# Wacky_Racer_Schematic.net
KiCad netlist of a schematic drawn in Altium Designer
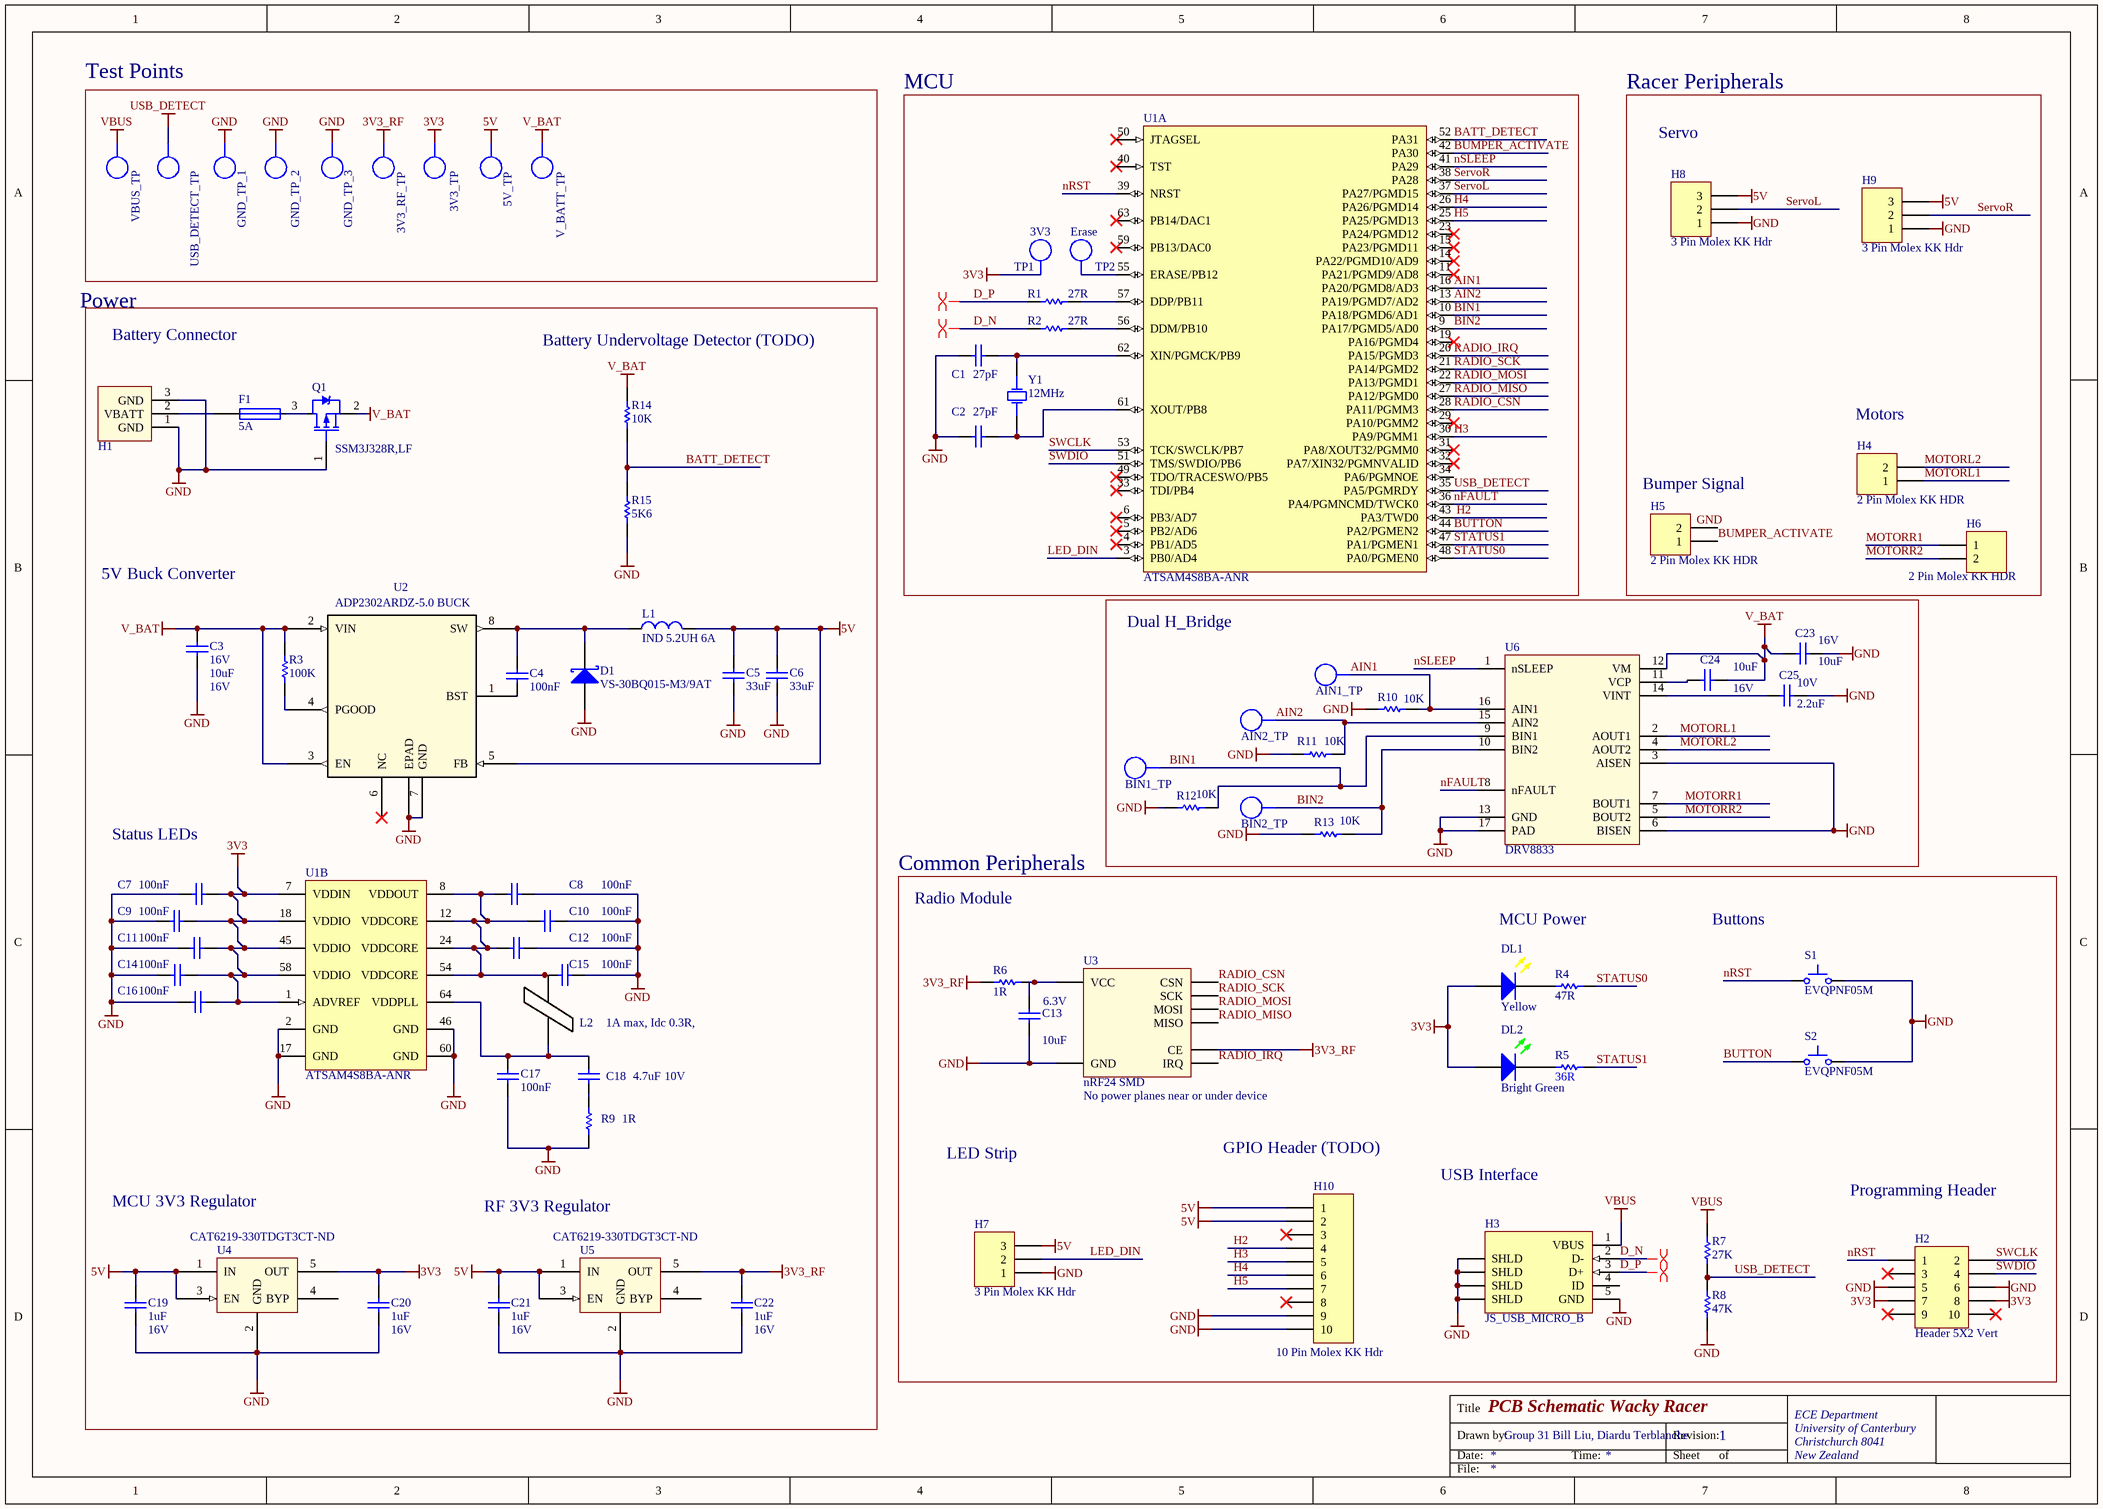
[diagram p0: Wacky Racer Schematic.schdoc]

(export (version "E")
  (design (tool "Eeschema 10.0.6"))
  (components
    (comp (ref "3V3_RF_TP")
      (value "TP")
      (footprint "TP_1206")
      (description "Test-Point 3.3x1.6x2.1mm SMD")
      (fields
        (field (name "MANUFACTURER") "Harwin Inc")
        (field (name "MANUFACTURER PART NUMBER") "S1751-46R")
      )
      (libsource (lib "ECE AD19Components_19V1") (part "TP_1206"))
    )
    (comp (ref "3V3_TP")
      (value "TP")
      (footprint "TP_1206")
      (description "Test-Point 3.3x1.6x2.1mm SMD")
      (fields
        (field (name "MANUFACTURER") "Harwin Inc")
        (field (name "MANUFACTURER PART NUMBER") "S1751-46R")
      )
      (libsource (lib "ECE AD19Components_19V1") (part "TP_1206"))
    )
    (comp (ref "5V_TP")
      (value "TP")
      (footprint "TP_1206")
      (description "Test-Point 3.3x1.6x2.1mm SMD")
      (fields
        (field (name "MANUFACTURER") "Harwin Inc")
        (field (name "MANUFACTURER PART NUMBER") "S1751-46R")
      )
      (libsource (lib "ECE AD19Components_19V1") (part "TP_1206"))
    )
    (comp (ref "AIN1_TP")
      (value "TP")
      (footprint "TP_1206")
      (description "Test-Point 3.3x1.6x2.1mm SMD")
      (fields
        (field (name "MANUFACTURER") "Harwin Inc")
        (field (name "MANUFACTURER PART NUMBER") "S1751-46R")
      )
      (libsource (lib "ECE AD19Components_19V1") (part "TP_1206"))
    )
    (comp (ref "AIN2_TP")
      (value "TP")
      (footprint "TP_1206")
      (description "Test-Point 3.3x1.6x2.1mm SMD")
      (fields
        (field (name "MANUFACTURER") "Harwin Inc")
        (field (name "MANUFACTURER PART NUMBER") "S1751-46R")
      )
      (libsource (lib "ECE AD19Components_19V1") (part "TP_1206"))
    )
    (comp (ref "BIN1_TP")
      (value "TP")
      (footprint "TP_1206")
      (description "Test-Point 3.3x1.6x2.1mm SMD")
      (fields
        (field (name "MANUFACTURER") "Harwin Inc")
        (field (name "MANUFACTURER PART NUMBER") "S1751-46R")
      )
      (libsource (lib "ECE AD19Components_19V1") (part "TP_1206"))
    )
    (comp (ref "BIN2_TP")
      (value "TP")
      (footprint "TP_1206")
      (description "Test-Point 3.3x1.6x2.1mm SMD")
      (fields
        (field (name "MANUFACTURER") "Harwin Inc")
        (field (name "MANUFACTURER PART NUMBER") "S1751-46R")
      )
      (libsource (lib "ECE AD19Components_19V1") (part "TP_1206"))
    )
    (comp (ref "C1")
      (value "27pF")
      (footprint "CAPC1608L")
      (description "CAP CER 27pF NPO/COG +-5% 50V 0603")
      (libsource (lib "ECE AD19Components_19V1") (part "CC_27pF_0603"))
    )
    (comp (ref "C2")
      (value "27pF")
      (footprint "CAPC1608L")
      (description "CAP CER 27pF NPO/COG +-5% 50V 0603")
      (libsource (lib "ECE AD19Components_19V1") (part "CC_27pF_0603"))
    )
    (comp (ref "C3")
      (value "10uF")
      (footprint "CAPC2012L")
      (description "CAP CER 10uF X5R 16V 0805")
      (fields
        (field (name "MANUFACTURER") "Samsung Electro-Mechanics")
        (field (name "MANUFACTURER PART NUMBER") "CL21A106KOQNNWE")
        (field (name "VOLTAGE - RATED") "16V")
        (field (name "MAX VOLTAGE") "16V")
      )
      (libsource (lib "ENCE461AD19_19V2") (part "CC_10uF_16V_0805"))
    )
    (comp (ref "C4")
      (value "100nF")
      (footprint "CAPC1608L")
      (description "CAP CER 100nF X7R +-10% 50V 0603")
      (libsource (lib "ECE AD19Components_19V1") (part "CC_100nF_0603"))
    )
    (comp (ref "C5")
      (value "33uF")
      (footprint "CAPC2012L")
      (description "CAP CER 33uF X5R 6V3 0805")
      (fields
        (field (name "MANUFACTURER") "TDK Corporation")
        (field (name "MANUFACTURER PART NUMBER") "C2012X5R0J336M125AC")
      )
      (libsource (lib "ENCE461AD19_19V2") (part "CC_33uF_6V3_0805"))
    )
    (comp (ref "C6")
      (value "33uF")
      (footprint "CAPC2012L")
      (description "CAP CER 33uF X5R 6V3 0805")
      (fields
        (field (name "MANUFACTURER") "TDK Corporation")
        (field (name "MANUFACTURER PART NUMBER") "C2012X5R0J336M125AC")
      )
      (libsource (lib "ENCE461AD19_19V2") (part "CC_33uF_6V3_0805"))
    )
    (comp (ref "C7")
      (value "100nF")
      (footprint "CAPC1608L")
      (description "CAP CER 100nF X7R +-10% 50V 0603")
      (libsource (lib "ECE AD19Components_19V1") (part "CC_100nF_0603"))
    )
    (comp (ref "C8")
      (value "100nF")
      (footprint "CAPC1608L")
      (description "CAP CER 100nF X7R +-10% 50V 0603")
      (libsource (lib "ECE AD19Components_19V1") (part "CC_100nF_0603"))
    )
    (comp (ref "C9")
      (value "100nF")
      (footprint "CAPC1608L")
      (description "CAP CER 100nF X7R +-10% 50V 0603")
      (libsource (lib "ECE AD19Components_19V1") (part "CC_100nF_0603"))
    )
    (comp (ref "C10")
      (value "100nF")
      (footprint "CAPC1608L")
      (description "CAP CER 100nF X7R +-10% 50V 0603")
      (libsource (lib "ECE AD19Components_19V1") (part "CC_100nF_0603"))
    )
    (comp (ref "C11")
      (value "100nF")
      (footprint "CAPC1608L")
      (description "CAP CER 100nF X7R +-10% 50V 0603")
      (libsource (lib "ECE AD19Components_19V1") (part "CC_100nF_0603"))
    )
    (comp (ref "C12")
      (value "100nF")
      (footprint "CAPC1608L")
      (description "CAP CER 100nF X7R +-10% 50V 0603")
      (libsource (lib "ECE AD19Components_19V1") (part "CC_100nF_0603"))
    )
    (comp (ref "C13")
      (value "10uF")
      (footprint "CAPC1608L")
      (description "CAP CER 10UF X5R +-20% 6V3 0603")
      (fields (field (name "VOLTAGE - RATED") "6.3V"))
      (libsource (lib "ECE AD19Components_19V1") (part "CC_10uF_0603"))
    )
    (comp (ref "C14")
      (value "100nF")
      (footprint "CAPC1608L")
      (description "CAP CER 100nF X7R +-10% 50V 0603")
      (libsource (lib "ECE AD19Components_19V1") (part "CC_100nF_0603"))
    )
    (comp (ref "C15")
      (value "100nF")
      (footprint "CAPC1608L")
      (description "CAP CER 100nF X7R +-10% 50V 0603")
      (libsource (lib "ECE AD19Components_19V1") (part "CC_100nF_0603"))
    )
    (comp (ref "C16")
      (value "100nF")
      (footprint "CAPC1608L")
      (description "CAP CER 100nF X7R +-10% 50V 0603")
      (libsource (lib "ECE AD19Components_19V1") (part "CC_100nF_0603"))
    )
    (comp (ref "C17")
      (value "100nF")
      (footprint "CAPC1608L")
      (description "CAP CER 100nF X7R +-10% 50V 0603")
      (libsource (lib "ECE AD19Components_19V1") (part "CC_100nF_0603"))
    )
    (comp (ref "C18")
      (value "4.7uF")
      (footprint "CAPC1608N")
      (description "CAP CER 4.7uF X5R +-20%  10V 0603")
      (fields (field (name "MAX VOLTAGE") "10V"))
      (libsource (lib "ECE AD19Components_19V1") (part "CC_4.7uF_0603"))
    )
    (comp (ref "C19")
      (value "1uF")
      (footprint "CAPC1608L")
      (description "CAP CER 1uF Y5V -20% +80% 16V 0603")
      (fields (field (name "MAX VOLTAGE") "16V"))
      (libsource (lib "ECE AD19Components_19V1") (part "CC_1uF_0603"))
    )
    (comp (ref "C20")
      (value "1uF")
      (footprint "CAPC1608L")
      (description "CAP CER 1uF Y5V -20% +80% 16V 0603")
      (fields (field (name "MAX VOLTAGE") "16V"))
      (libsource (lib "ECE AD19Components_19V1") (part "CC_1uF_0603"))
    )
    (comp (ref "C21")
      (value "1uF")
      (footprint "CAPC1608L")
      (description "CAP CER 1uF Y5V -20% +80% 16V 0603")
      (fields (field (name "MAX VOLTAGE") "16V"))
      (libsource (lib "ECE AD19Components_19V1") (part "CC_1uF_0603"))
    )
    (comp (ref "C22")
      (value "1uF")
      (footprint "CAPC1608L")
      (description "CAP CER 1uF Y5V -20% +80% 16V 0603")
      (fields (field (name "MAX VOLTAGE") "16V"))
      (libsource (lib "ECE AD19Components_19V1") (part "CC_1uF_0603"))
    )
    (comp (ref "C23")
      (value "10uF")
      (footprint "CAPC2012L")
      (description "CAP CER 10uF X5R 16V 0805")
      (fields
        (field (name "MANUFACTURER") "Samsung Electro-Mechanics")
        (field (name "MANUFACTURER PART NUMBER") "CL21A106KOQNNWE")
        (field (name "VOLTAGE - RATED") "16V")
      )
      (libsource (lib "ENCE461AD19_19V2") (part "CC_10uF_16V_0805"))
    )
    (comp (ref "C24")
      (value "10uF")
      (footprint "CAPC2012L")
      (description "CAP CER 10uF X5R 16V 0805")
      (fields
        (field (name "MANUFACTURER") "Samsung Electro-Mechanics")
        (field (name "MANUFACTURER PART NUMBER") "CL21A106KOQNNWE")
        (field (name "VOLTAGE - RATED") "16V")
      )
      (libsource (lib "ENCE461AD19_19V2") (part "CC_10uF_16V_0805"))
    )
    (comp (ref "C25")
      (value "2.2uF")
      (footprint "CAPC1608L")
      (description "CAP CER 2.2uF X5R +-20% 10V 0603")
      (fields (field (name "MAX VOLTAGE") "10V"))
      (libsource (lib "ECE AD19Components_19V1") (part "CC_2.2uF_0603"))
    )
    (comp (ref "D1")
      (value "VS-30BQ015-M3/9AT")
      (footprint "SMC")
      (description "DIODE, SCHOTTKY, 3A, 15V, DO-214AB / SMC")
      (fields (field (name "MANUFACTURER") "Vishay Semiconductors"))
      (libsource (lib "ECE AD19Components_19V1") (part "DS_VS-30BQ015-M3"))
    )
    (comp (ref "DL1")
      (value "Yellow")
      (footprint "WL-SMCW0603")
      (description "LED Yellow 120mcd 0603 SMD")
      (fields
        (field (name "MANUFACTURER") "WURTH ELEKTRONIK")
        (field (name "MANUFACTURER PART NUMBER") "150060YS75000")
        (field (name "LED COLOUR") "Yellow")
      )
      (libsource (lib "ECE AD19Components_19V1") (part "DL_150060YS75000"))
    )
    (comp (ref "DL2")
      (value "Bright Green")
      (footprint "WL-SMCW0603")
      (description "LED Bright Green 40mcd 0603 SMD")
      (fields
        (field (name "MANUFACTURER") "WURTH ELEKTRONIK")
        (field (name "MANUFACTURER PART NUMBER") "150060VS75000")
        (field (name "LED COLOUR") "Bright Green")
      )
      (libsource (lib "ECE AD19Components_19V1") (part "DL_150060VS75000"))
    )
    (comp (ref "F1")
      (value "5A")
      (footprint "RESC3216N")
      (description "Fuse 5.0A Fast Acting 1206 SMD")
      (fields (field (name "MANUFACTURER PART NUMBER") "C1F5") (field (name "MANUFACTURER") "Bel TRP"))
      (libsource (lib "ECE AD19Components_19V1") (part "FS_Fuse_5.0A"))
    )
    (comp (ref "GND_TP_1")
      (value "TP")
      (footprint "TP_1206")
      (description "Test-Point 3.3x1.6x2.1mm SMD")
      (fields
        (field (name "MANUFACTURER") "Harwin Inc")
        (field (name "MANUFACTURER PART NUMBER") "S1751-46R")
      )
      (libsource (lib "ECE AD19Components_19V1") (part "TP_1206"))
    )
    (comp (ref "GND_TP_2")
      (value "TP")
      (footprint "TP_1206")
      (description "Test-Point 3.3x1.6x2.1mm SMD")
      (fields
        (field (name "MANUFACTURER") "Harwin Inc")
        (field (name "MANUFACTURER PART NUMBER") "S1751-46R")
      )
      (libsource (lib "ECE AD19Components_19V1") (part "TP_1206"))
    )
    (comp (ref "GND_TP_3")
      (value "TP")
      (footprint "TP_1206")
      (description "Test-Point 3.3x1.6x2.1mm SMD")
      (fields
        (field (name "MANUFACTURER") "Harwin Inc")
        (field (name "MANUFACTURER PART NUMBER") "S1751-46R")
      )
      (libsource (lib "ECE AD19Components_19V1") (part "TP_1206"))
    )
    (comp (ref "H1")
      (value "Battery_HEADER_3pin")
      (footprint "BATT_HEADER_3POS")
      (description "3Pin Header 2.54mm spacing")
      (libsource (lib "ENCE461AD19_19V2") (part "Battery_HEADER_3pin"))
    )
    (comp (ref "H2")
      (value "Header 5X2 Vert")
      (footprint "IDC2.54-V10D")
      (description "IDC Header, 2,54mm, 10-Pin, Vert")
      (libsource (lib "ECE AD19Components_19V1") (part "JA_HDR_IDC_5X2_VERT"))
    )
    (comp (ref "H3")
      (value "JS_USB_MICRO_B")
      (footprint "FCI_USB_10118194-0001LF")
      (description "CONN USB MICRO B RECPT SMT R/A")
      (fields (field (name "MANUFACTURER") "FCI") (field (name "MANUFACTURER PART NUMBER") "10118194-0001LF"))
      (libsource (lib "ECE AD19Components_19V1") (part "JS_USB_MICRO_B_SMT"))
    )
    (comp (ref "H4")
      (value "2 Pin Molex KK HDR")
      (footprint "MOLEX_KK_2_HDR")
      (description "CONN HEADER 2POS 2.54mm VERT_Thru Hole")
      (libsource (lib "") (part "JA_MOLEX_KK_2POS_1"))
    )
    (comp (ref "H5")
      (value "2 Pin Molex KK HDR")
      (footprint "MOLEX_KK_2_HDR")
      (description "CONN HEADER 2POS 2.54mm VERT_Thru Hole")
      (libsource (lib "") (part "JA_MOLEX_KK_2POS_1"))
    )
    (comp (ref "H6")
      (value "2 Pin Molex KK HDR")
      (footprint "MOLEX_KK_2_HDR")
      (description "CONN HEADER 2POS 2.54mm VERT_Thru Hole")
      (libsource (lib "ECE AD19Components_19V1") (part "JA_MOLEX_KK_2POS"))
    )
    (comp (ref "H7")
      (value "3 Pin Molex KK Hdr")
      (footprint "MOLEX_KK_3_HDR")
      (description "CONN HEADER 3POS 2.54mm VERT_Thru Hole")
      (fields (field (name "MANUFACTURER") "Molex"))
      (libsource (lib "ECE AD19Components_19V1") (part "JA_MOLEX_KK_3POS"))
    )
    (comp (ref "H8")
      (value "3 Pin Molex KK Hdr")
      (footprint "MOLEX_KK_3_HDR")
      (description "CONN HEADER 3POS 2.54mm VERT_Thru Hole")
      (fields (field (name "MANUFACTURER") "Molex"))
      (libsource (lib "ECE AD19Components_19V1") (part "JA_MOLEX_KK_3POS"))
    )
    (comp (ref "H9")
      (value "3 Pin Molex KK Hdr")
      (footprint "MOLEX_KK_3_HDR")
      (description "CONN HEADER 3POS 2.54mm VERT_Thru Hole")
      (fields (field (name "MANUFACTURER") "Molex"))
      (libsource (lib "ECE AD19Components_19V1") (part "JA_MOLEX_KK_3POS"))
    )
    (comp (ref "H10")
      (value "10 Pin Molex KK Hdr")
      (footprint "MOLEX_KK_10_HDR")
      (description "CONN HEADER 10POS 2.54mm VERT_ Thru Hole")
      (libsource (lib "ECE AD19Components_19V1") (part "JA_MOLEX_KK_10POS"))
    )
    (comp (ref "L1")
      (value "IND 5.2UH 6A")
      (footprint "INDUCTOR5u2")
      (description "FIXED IND 5.2UH 6A 22 MOHM SMD")
      (fields
        (field (name "MANUFACTURER") "Sumida America Components Inc.")
        (field (name "MANUFACTURER PART NUMBER") "CDRH104RNP-5R2NC")
      )
      (libsource (lib "ENCE461AD19_19V2") (part "CDRH104RNP-5R2NC"))
    )
    (comp (ref "L2")
      (value "1A max, Idc 0.3R,")
      (footprint "INDC3216L")
      (description "Ferrite Bead, Rdc 0.3R, Z100MHZ 600R, Imax 1A, SMD 1206")
      (fields
        (field (name "MANUFACTURER") "FAIR-RITE")
        (field (name "MANUFACTURER PART NUMBER") "2512066017Y1")
      )
      (libsource (lib "ECE AD19Components_19V1") (part "IN_Ferrite-Bead"))
    )
    (comp (ref "Q1")
      (value "SSM3J328R,LF")
      (footprint "SOT23_L")
      (description "MOSFET P-CH 20V 6A SOT23-3")
      (fields
        (field (name "MANUFACTURER") "Toshiba")
        (field (name "MANUFACTURER PART NUMBER") "SSM3J328R,LF")
      )
      (libsource (lib "ECE AD19Components_19V1") (part "TM_SSM3J328R"))
    )
    (comp (ref "R1")
      (value "27R")
      (footprint "RESC1608L")
      (description "RES 27 OHM 1/10W 5% 0603 SMD")
      (libsource (lib "ECE AD19Components_19V1") (part "RS_27R"))
    )
    (comp (ref "R2")
      (value "27R")
      (footprint "RESC1608L")
      (description "RES 27 OHM 1/10W 5% 0603 SMD")
      (libsource (lib "ECE AD19Components_19V1") (part "RS_27R"))
    )
    (comp (ref "R3")
      (value "100K")
      (footprint "RESC1608L")
      (description "RES 100K OHM 1/10W 5% 0603 SMD")
      (libsource (lib "ECE AD19Components_19V1") (part "RS_100K"))
    )
    (comp (ref "R4")
      (value "47R")
      (footprint "RESC1608L")
      (description "RES 47 OHM 1/10W 5% 0603 SMD")
      (libsource (lib "ECE AD19Components_19V1") (part "RS_47R"))
    )
    (comp (ref "R5")
      (value "36R")
      (footprint "RESC1608L")
      (description "RES 36 OHM 1/10W 5% 0603 SMD")
      (libsource (lib "ECE AD19Components_19V1") (part "RS_36R"))
    )
    (comp (ref "R6")
      (value "1R")
      (footprint "RESC3216L")
      (description "RES 1R OHM 1/4W 5% 1206 SMD")
      (libsource (lib "ECE AD19Components_19V1") (part "RT_1R"))
    )
    (comp (ref "R7")
      (value "27K")
      (footprint "RESC1608L")
      (description "RES 27K OHM 1/10W 5% 0603 SMD")
      (libsource (lib "ECE AD19Components_19V1") (part "RS_27K"))
    )
    (comp (ref "R8")
      (value "47K")
      (footprint "RESC1608N")
      (description "RES 47.0K OHM 1/10W 5% 0603 SMD")
      (libsource (lib "ECE AD19Components_19V1") (part "RS_47K"))
    )
    (comp (ref "R9")
      (value "1R")
      (footprint "RESC3216L")
      (description "RES 1R OHM 1/4W 5% 1206 SMD")
      (libsource (lib "ECE AD19Components_19V1") (part "RT_1R"))
    )
    (comp (ref "R10")
      (value "10K")
      (footprint "RESC1608L")
      (description "RES 10.0K OHM 1/10W 5% 0603 SMD")
      (libsource (lib "ECE AD19Components_19V1") (part "RS_10K"))
    )
    (comp (ref "R11")
      (value "10K")
      (footprint "RESC1608L")
      (description "RES 10.0K OHM 1/10W 5% 0603 SMD")
      (libsource (lib "ECE AD19Components_19V1") (part "RS_10K"))
    )
    (comp (ref "R12")
      (value "10K")
      (footprint "RESC1608L")
      (description "RES 10.0K OHM 1/10W 5% 0603 SMD")
      (libsource (lib "ECE AD19Components_19V1") (part "RS_10K"))
    )
    (comp (ref "R13")
      (value "10K")
      (footprint "RESC1608L")
      (description "RES 10.0K OHM 1/10W 5% 0603 SMD")
      (libsource (lib "ECE AD19Components_19V1") (part "RS_10K"))
    )
    (comp (ref "R14")
      (value "10K")
      (footprint "RESC1608L")
      (description "RES 10.0K OHM 1/10W 5% 0603 SMD")
      (libsource (lib "ECE AD19Components_19V1") (part "RS_10K"))
    )
    (comp (ref "R15")
      (value "5K6")
      (footprint "RESC1608L")
      (description "RES 5.6K OHM 1/10W 5% 0603 SMD")
      (libsource (lib "ECE AD19Components_19V1") (part "RS_5K6"))
    )
    (comp (ref "S1")
      (value "EVQPNF05M")
      (footprint "EVQPNF05M")
      (description "Panasonic 6 x 3.5mm SMD Light Touch Switch Type SMD")
      (fields (field (name "MANUFACTURER") "Panasonic"))
      (libsource (lib "ECE AD19Components_19V1") (part "WS_EVQPNF05M"))
    )
    (comp (ref "S2")
      (value "EVQPNF05M")
      (footprint "EVQPNF05M")
      (description "Panasonic 6 x 3.5mm SMD Light Touch Switch Type SMD")
      (fields (field (name "MANUFACTURER") "Panasonic"))
      (libsource (lib "ECE AD19Components_19V1") (part "WS_EVQPNF05M"))
    )
    (comp (ref "TP1")
      (value "3V3")
      (footprint "TP_1206")
      (description "Test-Point 3.3x1.6x2.1mm SMD")
      (fields
        (field (name "MANUFACTURER") "Harwin Inc")
        (field (name "MANUFACTURER PART NUMBER") "S1751-46R")
      )
      (libsource (lib "ECE AD19Components_19V1") (part "TP_1206"))
    )
    (comp (ref "TP2")
      (value "Erase")
      (footprint "TP_1206")
      (description "Test-Point 3.3x1.6x2.1mm SMD")
      (fields
        (field (name "MANUFACTURER") "Harwin Inc")
        (field (name "MANUFACTURER PART NUMBER") "S1751-46R")
      )
      (libsource (lib "ECE AD19Components_19V1") (part "TP_1206"))
    )
    (comp (ref "U1")
      (value "ATSAM4S8BA-ANR")
      (footprint "LQFP64_L")
      (description "IC MCU 32BIT 512KB FLASH 64LQFP")
      (fields (field (name "MANUFACTURER") "Atmel"))
      (libsource (lib "ECE AD19Components_19V1") (part "SE_ATSAM4S16BA-MU"))
    )
    (comp (ref "U2")
      (value "ADP2302ARDZ-5.0 BUCK")
      (footprint "RD_8_1")
      (description "IC REG BUCK 5V 2A 8SOIC")
      (fields (field (name "MANUFACTURER_PART_NUMBER") "ADP2302ARDZ-5.0-R7"))
      (libsource (lib "ENCE461AD19_19V2") (part "ADP2302ARDZ-5.0-R7"))
    )
    (comp (ref "U3")
      (value "nRF24 SMD")
      (footprint "NRF24")
      (description "nRF24 SMD Module")
      (fields (field (name "WARNING") "No power planes near or under device"))
      (libsource (lib "ENCE461AD19_19V2") (part "NRF24"))
    )
    (comp (ref "U4")
      (value "CAT6219-330TDGT3")
      (footprint "SOT95P280X145-5N")
      (description "IC REG LIN 3.3V 500MA TSOT23-5")
      (fields
        (field (name "BASE PART NUMBER") "CAT6219")
        (field (name "SUPPLIER PART NUMBER") "CAT6219-330TDGT3CT-ND")
      )
      (libsource (lib "ENCE461AD19_19V2") (part "SV_CAT6219-330TDGT3"))
    )
    (comp (ref "U5")
      (value "CAT6219-330TDGT3")
      (footprint "SOT95P280X145-5N")
      (description "IC REG LIN 3.3V 500MA TSOT23-5")
      (fields
        (field (name "BASE PART NUMBER") "CAT6219")
        (field (name "SUPPLIER PART NUMBER") "CAT6219-330TDGT3CT-ND")
      )
      (libsource (lib "ENCE461AD19_19V2") (part "SV_CAT6219-330TDGT3"))
    )
    (comp (ref "U6")
      (value "DRV8833")
      (footprint "HTSOP16")
      (description "Dual H-Bridge Motor Driver 1.5A")
      (libsource (lib "ENCE461AD19_19V2") (part "DRV8833"))
    )
    (comp (ref "USB_DETECT_TP")
      (value "TP")
      (footprint "TP_1206")
      (description "Test-Point 3.3x1.6x2.1mm SMD")
      (fields
        (field (name "MANUFACTURER") "Harwin Inc")
        (field (name "MANUFACTURER PART NUMBER") "S1751-46R")
      )
      (libsource (lib "ECE AD19Components_19V1") (part "TP_1206"))
    )
    (comp (ref "VBUS_TP")
      (value "TP")
      (footprint "TP_1206")
      (description "Test-Point 3.3x1.6x2.1mm SMD")
      (fields
        (field (name "MANUFACTURER") "Harwin Inc")
        (field (name "MANUFACTURER PART NUMBER") "S1751-46R")
      )
      (libsource (lib "ECE AD19Components_19V1") (part "TP_1206"))
    )
    (comp (ref "V_BATT_TP")
      (value "TP")
      (footprint "TP_1206")
      (description "Test-Point 3.3x1.6x2.1mm SMD")
      (fields
        (field (name "MANUFACTURER") "Harwin Inc")
        (field (name "MANUFACTURER PART NUMBER") "S1751-46R")
      )
      (libsource (lib "ECE AD19Components_19V1") (part "TP_1206"))
    )
    (comp (ref "Y1")
      (value "12MHz")
      (footprint "6.0X3.5-4")
      (description "CRYSTAL 12MHZ 18PF 6X3.5mm SMD")
      (fields
        (field (name "MANUFACTURER") "CTS-Frequency Controls")
        (field (name "MANUFACTURER PART NUMBER") "406C35D12M00000")
        (field (name "FREQUENCY") "12MHz")
      )
      (libsource (lib "ECE AD19Components_19V1") (part "XT_CRYSTAL_12MHz_18pF"))
    )
  )
  (nets
    (net (code "1") (name "/AIN1") (class "Default")
      (node (ref "AIN1_TP") (pin "1") (pinfunction "1_1") (pintype "passive"))
      (node (ref "R10") (pin "2") (pinfunction "2_2") (pintype "passive"))
      (node (ref "U1") (pin "16") (pinfunction "PA20/PGMD8/AD3_16") (pintype "bidirectional"))
      (node (ref "U6") (pin "16") (pinfunction "AIN1_16") (pintype "passive"))
    )
    (net (code "2") (name "/AIN2") (class "Default")
      (node (ref "AIN2_TP") (pin "1") (pinfunction "1_1") (pintype "passive"))
      (node (ref "R11") (pin "2") (pinfunction "2_2") (pintype "passive"))
      (node (ref "U1") (pin "13") (pinfunction "PA19/PGMD7/AD2_13") (pintype "bidirectional"))
      (node (ref "U6") (pin "15") (pinfunction "AIN2_15") (pintype "passive"))
    )
    (net (code "3") (name "/BATT_DETECT") (class "Default")
      (node (ref "R14") (pin "1") (pinfunction "1_1") (pintype "passive"))
      (node (ref "R15") (pin "2") (pinfunction "2_2") (pintype "passive"))
      (node (ref "U1") (pin "52") (pinfunction "PA31_52") (pintype "bidirectional"))
    )
    (net (code "4") (name "/BIN1") (class "Default")
      (node (ref "BIN1_TP") (pin "1") (pinfunction "1_1") (pintype "passive"))
      (node (ref "R12") (pin "2") (pinfunction "2_2") (pintype "passive"))
      (node (ref "U1") (pin "10") (pinfunction "PA18/PGMD6/AD1_10") (pintype "bidirectional"))
      (node (ref "U6") (pin "9") (pinfunction "BIN1_9") (pintype "passive"))
    )
    (net (code "5") (name "/BIN2") (class "Default")
      (node (ref "BIN2_TP") (pin "1") (pinfunction "1_1") (pintype "passive"))
      (node (ref "R13") (pin "2") (pinfunction "2_2") (pintype "passive"))
      (node (ref "U1") (pin "9") (pinfunction "PA17/PGMD5/AD0_9") (pintype "bidirectional"))
      (node (ref "U6") (pin "10") (pinfunction "BIN2_10") (pintype "passive"))
    )
    (net (code "6") (name "/BUMPER_ACTIVATE") (class "Default")
      (node (ref "H5") (pin "1") (pinfunction "1_1") (pintype "passive"))
      (node (ref "U1") (pin "42") (pinfunction "PA30_42") (pintype "bidirectional"))
    )
    (net (code "7") (name "/BUTTON") (class "Default")
      (node (ref "S2") (pin "1") (pintype "passive"))
      (node (ref "U1") (pin "44") (pinfunction "PA2/PGMEN2_44") (pintype "bidirectional"))
    )
    (net (code "8") (name "/D_N") (class "Default")
      (node (ref "H3") (pin "2") (pinfunction "D-_2") (pintype "input"))
      (node (ref "R2") (pin "1") (pinfunction "1_1") (pintype "passive"))
    )
    (net (code "9") (name "/D_P") (class "Default")
      (node (ref "H3") (pin "3") (pinfunction "D+_3") (pintype "input"))
      (node (ref "R1") (pin "1") (pinfunction "1_1") (pintype "passive"))
    )
    (net (code "10") (name "/H2") (class "Default")
      (node (ref "H10") (pin "4") (pinfunction "4_4") (pintype "passive"))
      (node (ref "U1") (pin "43") (pinfunction "PA3/TWD0_43") (pintype "bidirectional"))
    )
    (net (code "11") (name "/H3") (class "Default")
      (node (ref "H10") (pin "5") (pinfunction "5_5") (pintype "passive"))
      (node (ref "U1") (pin "30") (pinfunction "PA9/PGMM1_30") (pintype "bidirectional"))
    )
    (net (code "12") (name "/H4") (class "Default")
      (node (ref "H10") (pin "6") (pinfunction "6_6") (pintype "passive"))
      (node (ref "U1") (pin "26") (pinfunction "PA26/PGMD14_26") (pintype "bidirectional"))
    )
    (net (code "13") (name "/H5") (class "Default")
      (node (ref "H10") (pin "7") (pinfunction "7_7") (pintype "passive"))
      (node (ref "U1") (pin "25") (pinfunction "PA25/PGMD13_25") (pintype "bidirectional"))
    )
    (net (code "14") (name "/LED_DIN") (class "Default")
      (node (ref "H7") (pin "2") (pinfunction "2_2") (pintype "passive"))
      (node (ref "U1") (pin "3") (pinfunction "PB0/AD4_3") (pintype "bidirectional"))
    )
    (net (code "15") (name "/MOTORL1") (class "Default")
      (node (ref "H4") (pin "1") (pinfunction "1_1") (pintype "passive"))
      (node (ref "U6") (pin "2") (pinfunction "AOUT1_2") (pintype "passive"))
    )
    (net (code "16") (name "/MOTORL2") (class "Default")
      (node (ref "H4") (pin "2") (pinfunction "2_2") (pintype "passive"))
      (node (ref "U6") (pin "4") (pinfunction "AOUT2_4") (pintype "passive"))
    )
    (net (code "17") (name "/MOTORR1") (class "Default")
      (node (ref "H6") (pin "1") (pinfunction "1_1") (pintype "passive"))
      (node (ref "U6") (pin "7") (pinfunction "BOUT1_7") (pintype "passive"))
    )
    (net (code "18") (name "/MOTORR2") (class "Default")
      (node (ref "H6") (pin "2") (pinfunction "2_2") (pintype "passive"))
      (node (ref "U6") (pin "5") (pinfunction "BOUT2_5") (pintype "passive"))
    )
    (net (code "19") (name "/RADIO_CSN") (class "Default")
      (node (ref "U1") (pin "28") (pinfunction "PA11/PGMM3_28") (pintype "bidirectional"))
      (node (ref "U3") (pin "4") (pinfunction "CSN_4") (pintype "passive"))
    )
    (net (code "20") (name "/RADIO_IRQ") (class "Default")
      (node (ref "U1") (pin "20") (pinfunction "PA15/PGMD3_20") (pintype "bidirectional"))
      (node (ref "U3") (pin "8") (pinfunction "IRQ_8") (pintype "passive"))
    )
    (net (code "21") (name "/RADIO_MISO") (class "Default")
      (node (ref "U1") (pin "27") (pinfunction "PA12/PGMD0_27") (pintype "bidirectional"))
      (node (ref "U3") (pin "7") (pinfunction "MISO_7") (pintype "passive"))
    )
    (net (code "22") (name "/RADIO_MOSI") (class "Default")
      (node (ref "U1") (pin "22") (pinfunction "PA13/PGMD1_22") (pintype "bidirectional"))
      (node (ref "U3") (pin "6") (pinfunction "MOSI_6") (pintype "passive"))
    )
    (net (code "23") (name "/RADIO_SCK") (class "Default")
      (node (ref "U1") (pin "21") (pinfunction "PA14/PGMD2_21") (pintype "bidirectional"))
      (node (ref "U3") (pin "5") (pinfunction "SCK_5") (pintype "passive"))
    )
    (net (code "24") (name "/STATUS0") (class "Default")
      (node (ref "R4") (pin "2") (pinfunction "2_2") (pintype "passive"))
      (node (ref "U1") (pin "48") (pinfunction "PA0/PGMEN0_48") (pintype "bidirectional"))
    )
    (net (code "25") (name "/STATUS1") (class "Default")
      (node (ref "R5") (pin "2") (pinfunction "2_2") (pintype "passive"))
      (node (ref "U1") (pin "47") (pinfunction "PA1/PGMEN1_47") (pintype "bidirectional"))
    )
    (net (code "26") (name "/SWCLK") (class "Default")
      (node (ref "H2") (pin "2") (pinfunction "2_2") (pintype "passive"))
      (node (ref "U1") (pin "53") (pinfunction "TCK/SWCLK/PB7_53") (pintype "bidirectional"))
    )
    (net (code "27") (name "/SWDIO") (class "Default")
      (node (ref "H2") (pin "4") (pinfunction "4_4") (pintype "passive"))
      (node (ref "U1") (pin "51") (pinfunction "TMS/SWDIO/PB6_51") (pintype "bidirectional"))
    )
    (net (code "28") (name "/ServoL") (class "Default")
      (node (ref "H8") (pin "2") (pinfunction "2_2") (pintype "passive"))
      (node (ref "U1") (pin "37") (pinfunction "PA27/PGMD15_37") (pintype "bidirectional"))
    )
    (net (code "29") (name "/ServoR") (class "Default")
      (node (ref "H9") (pin "2") (pinfunction "2_2") (pintype "passive"))
      (node (ref "U1") (pin "38") (pinfunction "PA28_38") (pintype "bidirectional"))
    )
    (net (code "30") (name "/nFAULT") (class "Default")
      (node (ref "U1") (pin "36") (pinfunction "PA4/PGMNCMD/TWCK0_36") (pintype "bidirectional"))
      (node (ref "U6") (pin "8") (pinfunction "nFAULT_8") (pintype "passive"))
    )
    (net (code "31") (name "/nRST") (class "Default")
      (node (ref "H2") (pin "1") (pinfunction "1_1") (pintype "passive"))
      (node (ref "S1") (pin "1") (pintype "passive"))
      (node (ref "U1") (pin "39") (pinfunction "NRST_39") (pintype "bidirectional"))
    )
    (net (code "32") (name "/nSLEEP") (class "Default")
      (node (ref "U1") (pin "41") (pinfunction "PA29_41") (pintype "bidirectional"))
      (node (ref "U6") (pin "1") (pinfunction "nSLEEP_1") (pintype "passive"))
    )
    (net (code "33") (name "3V3") (class "Default")
      (node (ref "3V3_TP") (pin "1") (pinfunction "1_1") (pintype "passive"))
      (node (ref "C11") (pin "2") (pinfunction "2_2") (pintype "passive"))
      (node (ref "C14") (pin "2") (pinfunction "2_2") (pintype "passive"))
      (node (ref "C16") (pin "2") (pinfunction "2_2") (pintype "passive"))
      (node (ref "C20") (pin "2") (pinfunction "2_2") (pintype "passive"))
      (node (ref "C7") (pin "2") (pinfunction "2_2") (pintype "passive"))
      (node (ref "C9") (pin "2") (pinfunction "2_2") (pintype "passive"))
      (node (ref "DL1") (pin "2") (pinfunction "A_2") (pintype "passive"))
      (node (ref "DL2") (pin "2") (pinfunction "A_2") (pintype "passive"))
      (node (ref "H2") (pin "7") (pinfunction "7_7") (pintype "passive"))
      (node (ref "H2") (pin "8") (pinfunction "8_8") (pintype "passive"))
      (node (ref "TP1") (pin "1") (pinfunction "1_1") (pintype "passive"))
      (node (ref "U1") (pin "1") (pinfunction "ADVREF_1") (pintype "input"))
      (node (ref "U1") (pin "18") (pinfunction "VDDIO_18") (pintype "power_in"))
      (node (ref "U1") (pin "45") (pinfunction "VDDIO_45") (pintype "power_in"))
      (node (ref "U1") (pin "58") (pinfunction "VDDIO_58") (pintype "power_in"))
      (node (ref "U1") (pin "7") (pinfunction "VDDIN_7") (pintype "power_in"))
      (node (ref "U4") (pin "5") (pinfunction "OUT_5") (pintype "power_in"))
    )
    (net (code "34") (name "3V3_RF") (class "Default")
      (node (ref "3V3_RF_TP") (pin "1") (pinfunction "1_1") (pintype "passive"))
      (node (ref "C22") (pin "2") (pinfunction "2_2") (pintype "passive"))
      (node (ref "R6") (pin "1") (pinfunction "1_1") (pintype "passive"))
      (node (ref "U3") (pin "3") (pinfunction "CE_3") (pintype "passive"))
      (node (ref "U5") (pin "5") (pinfunction "OUT_5") (pintype "power_in"))
    )
    (net (code "35") (name "5V") (class "Default")
      (node (ref "5V_TP") (pin "1") (pinfunction "1_1") (pintype "passive"))
      (node (ref "C19") (pin "2") (pinfunction "2_2") (pintype "passive"))
      (node (ref "C21") (pin "2") (pinfunction "2_2") (pintype "passive"))
      (node (ref "C5") (pin "2") (pinfunction "2_2") (pintype "passive"))
      (node (ref "C6") (pin "2") (pinfunction "2_2") (pintype "passive"))
      (node (ref "H10") (pin "1") (pinfunction "1_1") (pintype "passive"))
      (node (ref "H10") (pin "2") (pinfunction "2_2") (pintype "passive"))
      (node (ref "H7") (pin "3") (pinfunction "3_3") (pintype "passive"))
      (node (ref "H8") (pin "3") (pinfunction "3_3") (pintype "passive"))
      (node (ref "H9") (pin "3") (pinfunction "3_3") (pintype "passive"))
      (node (ref "L1") (pin "2") (pintype "passive"))
      (node (ref "U2") (pin "5") (pinfunction "FB_5") (pintype "input"))
      (node (ref "U4") (pin "1") (pinfunction "IN_1") (pintype "power_in"))
      (node (ref "U4") (pin "3") (pinfunction "EN_3") (pintype "input"))
      (node (ref "U5") (pin "1") (pinfunction "IN_1") (pintype "power_in"))
      (node (ref "U5") (pin "3") (pinfunction "EN_3") (pintype "input"))
    )
    (net (code "36") (name "GND") (class "Default")
      (node (ref "C1") (pin "1") (pinfunction "1_1") (pintype "passive"))
      (node (ref "C10") (pin "2") (pinfunction "2_2") (pintype "passive"))
      (node (ref "C11") (pin "1") (pinfunction "1_1") (pintype "passive"))
      (node (ref "C12") (pin "2") (pinfunction "2_2") (pintype "passive"))
      (node (ref "C13") (pin "1") (pinfunction "1_1") (pintype "passive"))
      (node (ref "C14") (pin "1") (pinfunction "1_1") (pintype "passive"))
      (node (ref "C15") (pin "2") (pinfunction "2_2") (pintype "passive"))
      (node (ref "C16") (pin "1") (pinfunction "1_1") (pintype "passive"))
      (node (ref "C17") (pin "1") (pinfunction "1_1") (pintype "passive"))
      (node (ref "C19") (pin "1") (pinfunction "1_1") (pintype "passive"))
      (node (ref "C2") (pin "1") (pinfunction "1_1") (pintype "passive"))
      (node (ref "C20") (pin "1") (pinfunction "1_1") (pintype "passive"))
      (node (ref "C21") (pin "1") (pinfunction "1_1") (pintype "passive"))
      (node (ref "C22") (pin "1") (pinfunction "1_1") (pintype "passive"))
      (node (ref "C23") (pin "2") (pinfunction "2_2") (pintype "passive"))
      (node (ref "C25") (pin "2") (pinfunction "2_2") (pintype "passive"))
      (node (ref "C3") (pin "1") (pinfunction "1_1") (pintype "passive"))
      (node (ref "C5") (pin "1") (pinfunction "1_1") (pintype "passive"))
      (node (ref "C6") (pin "1") (pinfunction "1_1") (pintype "passive"))
      (node (ref "C7") (pin "1") (pinfunction "1_1") (pintype "passive"))
      (node (ref "C8") (pin "2") (pinfunction "2_2") (pintype "passive"))
      (node (ref "C9") (pin "1") (pinfunction "1_1") (pintype "passive"))
      (node (ref "D1") (pin "1") (pinfunction "A_1") (pintype "passive"))
      (node (ref "GND_TP_1") (pin "1") (pinfunction "1_1") (pintype "passive"))
      (node (ref "GND_TP_2") (pin "1") (pinfunction "1_1") (pintype "passive"))
      (node (ref "GND_TP_3") (pin "1") (pinfunction "1_1") (pintype "passive"))
      (node (ref "H1") (pin "1") (pinfunction "GND_1") (pintype "passive"))
      (node (ref "H1") (pin "3") (pinfunction "GND_3") (pintype "passive"))
      (node (ref "H10") (pin "10") (pinfunction "10_10") (pintype "passive"))
      (node (ref "H10") (pin "9") (pinfunction "9_9") (pintype "passive"))
      (node (ref "H2") (pin "5") (pinfunction "5_5") (pintype "passive"))
      (node (ref "H2") (pin "6") (pinfunction "6_6") (pintype "passive"))
      (node (ref "H3") (pin "5") (pinfunction "GND_5") (pintype "passive"))
      (node (ref "H3") (pin "6") (pinfunction "SHLD_6") (pintype "passive"))
      (node (ref "H7") (pin "1") (pinfunction "1_1") (pintype "passive"))
      (node (ref "H8") (pin "1") (pinfunction "1_1") (pintype "passive"))
      (node (ref "H9") (pin "1") (pinfunction "1_1") (pintype "passive"))
      (node (ref "Q1") (pin "1") (pinfunction "1_1") (pintype "passive"))
      (node (ref "R10") (pin "1") (pinfunction "1_1") (pintype "passive"))
      (node (ref "R11") (pin "1") (pinfunction "1_1") (pintype "passive"))
      (node (ref "R12") (pin "1") (pinfunction "1_1") (pintype "passive"))
      (node (ref "R13") (pin "1") (pinfunction "1_1") (pintype "passive"))
      (node (ref "R15") (pin "1") (pinfunction "1_1") (pintype "passive"))
      (node (ref "R8") (pin "1") (pinfunction "1_1") (pintype "passive"))
      (node (ref "R9") (pin "1") (pinfunction "1_1") (pintype "passive"))
      (node (ref "S1") (pin "2") (pintype "passive"))
      (node (ref "S2") (pin "2") (pintype "passive"))
      (node (ref "U1") (pin "17") (pinfunction "GND_17") (pintype "power_in"))
      (node (ref "U1") (pin "2") (pinfunction "GND_2") (pintype "power_in"))
      (node (ref "U1") (pin "46") (pinfunction "GND_46") (pintype "power_in"))
      (node (ref "U1") (pin "60") (pinfunction "GND_60") (pintype "power_in"))
      (node (ref "U2") (pin "7") (pinfunction "GND_7") (pintype "power_in"))
      (node (ref "U2") (pin "EPAD") (pinfunction "EPAD_EPAD") (pintype "passive"))
      (node (ref "U3") (pin "2") (pinfunction "GND_2") (pintype "passive"))
      (node (ref "U4") (pin "2") (pinfunction "GND_2") (pintype "power_in"))
      (node (ref "U5") (pin "2") (pinfunction "GND_2") (pintype "power_in"))
      (node (ref "U6") (pin "13") (pinfunction "GND_13") (pintype "passive"))
      (node (ref "U6") (pin "17") (pinfunction "PAD_17") (pintype "passive"))
      (node (ref "U6") (pin "3") (pinfunction "AISEN_3") (pintype "passive"))
      (node (ref "U6") (pin "6") (pinfunction "BISEN_6") (pintype "passive"))
    )
    (net (code "37") (name "Net-(C18-Pad1)") (class "Default")
      (node (ref "C18") (pin "1") (pinfunction "1_1") (pintype "passive"))
      (node (ref "R9") (pin "2") (pinfunction "2_2") (pintype "passive"))
    )
    (net (code "38") (name "Net-(D1-K)") (class "Default")
      (node (ref "C4") (pin "2") (pinfunction "2_2") (pintype "passive"))
      (node (ref "D1") (pin "2") (pinfunction "K_2") (pintype "passive"))
      (node (ref "L1") (pin "1") (pintype "passive"))
      (node (ref "U2") (pin "8") (pinfunction "SW_8") (pintype "output"))
    )
    (net (code "39") (name "Net-(DL1-K)") (class "Default")
      (node (ref "DL1") (pin "1") (pinfunction "K_1") (pintype "passive"))
      (node (ref "R4") (pin "1") (pinfunction "1_1") (pintype "passive"))
    )
    (net (code "40") (name "Net-(DL2-K)") (class "Default")
      (node (ref "DL2") (pin "1") (pinfunction "K_1") (pintype "passive"))
      (node (ref "R5") (pin "1") (pinfunction "1_1") (pintype "passive"))
    )
    (net (code "41") (name "Net-(F1-Pad2)") (class "Default")
      (node (ref "F1") (pin "2") (pinfunction "2_2") (pintype "passive"))
      (node (ref "Q1") (pin "3") (pinfunction "3_3") (pintype "passive"))
    )
    (net (code "42") (name "Net-(H1-VBATT)") (class "Default")
      (node (ref "F1") (pin "1") (pinfunction "1_1") (pintype "passive"))
      (node (ref "H1") (pin "2") (pinfunction "VBATT_2") (pintype "passive"))
    )
    (net (code "43") (name "Net-(U1A-DDM{slash}PB10)") (class "Default")
      (node (ref "R2") (pin "2") (pinfunction "2_2") (pintype "passive"))
      (node (ref "U1") (pin "56") (pinfunction "DDM/PB10_56") (pintype "bidirectional"))
    )
    (net (code "44") (name "Net-(U1A-DDP{slash}PB11)") (class "Default")
      (node (ref "R1") (pin "2") (pinfunction "2_2") (pintype "passive"))
      (node (ref "U1") (pin "57") (pinfunction "DDP/PB11_57") (pintype "bidirectional"))
    )
    (net (code "45") (name "Net-(U1A-ERASE{slash}PB12)") (class "Default")
      (node (ref "TP2") (pin "1") (pinfunction "1_1") (pintype "passive"))
      (node (ref "U1") (pin "55") (pinfunction "ERASE/PB12_55") (pintype "bidirectional"))
    )
    (net (code "46") (name "Net-(U1A-XIN{slash}PGMCK{slash}PB9)") (class "Default")
      (node (ref "C1") (pin "2") (pinfunction "2_2") (pintype "passive"))
      (node (ref "U1") (pin "62") (pinfunction "XIN/PGMCK/PB9_62") (pintype "bidirectional"))
      (node (ref "Y1") (pin "1") (pinfunction "OSC1_1") (pintype "passive"))
    )
    (net (code "47") (name "Net-(U1A-XOUT{slash}PB8)") (class "Default")
      (node (ref "C2") (pin "2") (pinfunction "2_2") (pintype "passive"))
      (node (ref "U1") (pin "61") (pinfunction "XOUT/PB8_61") (pintype "bidirectional"))
      (node (ref "Y1") (pin "3") (pinfunction "OSC2_3") (pintype "passive"))
    )
    (net (code "48") (name "Net-(U1B-VDDOUT)") (class "Default")
      (node (ref "C10") (pin "1") (pinfunction "1_1") (pintype "passive"))
      (node (ref "C12") (pin "1") (pinfunction "1_1") (pintype "passive"))
      (node (ref "C15") (pin "1") (pinfunction "1_1") (pintype "passive"))
      (node (ref "C8") (pin "1") (pinfunction "1_1") (pintype "passive"))
      (node (ref "L2") (pin "2") (pinfunction "2_2") (pintype "passive"))
      (node (ref "U1") (pin "12") (pinfunction "VDDCORE_12") (pintype "power_in"))
      (node (ref "U1") (pin "24") (pinfunction "VDDCORE_24") (pintype "power_in"))
      (node (ref "U1") (pin "54") (pinfunction "VDDCORE_54") (pintype "power_in"))
      (node (ref "U1") (pin "8") (pinfunction "VDDOUT_8") (pintype "power_in"))
    )
    (net (code "49") (name "Net-(U1B-VDDPLL)") (class "Default")
      (node (ref "C17") (pin "2") (pinfunction "2_2") (pintype "passive"))
      (node (ref "C18") (pin "2") (pinfunction "2_2") (pintype "passive"))
      (node (ref "L2") (pin "1") (pinfunction "1_1") (pintype "passive"))
      (node (ref "U1") (pin "64") (pinfunction "VDDPLL_64") (pintype "power_in"))
    )
    (net (code "50") (name "Net-(U2-BST)") (class "Default")
      (node (ref "C4") (pin "1") (pinfunction "1_1") (pintype "passive"))
      (node (ref "U2") (pin "1") (pinfunction "BST_1") (pintype "passive"))
    )
    (net (code "51") (name "Net-(U2-PGOOD)") (class "Default")
      (node (ref "R3") (pin "1") (pinfunction "1_1") (pintype "passive"))
      (node (ref "U2") (pin "4") (pinfunction "PGOOD_4") (pintype "output"))
    )
    (net (code "52") (name "Net-(U3-VCC)") (class "Default")
      (node (ref "C13") (pin "2") (pinfunction "2_2") (pintype "passive"))
      (node (ref "R6") (pin "2") (pinfunction "2_2") (pintype "passive"))
      (node (ref "U3") (pin "1") (pinfunction "VCC_1") (pintype "passive"))
    )
    (net (code "53") (name "Net-(U6-VCP)") (class "Default")
      (node (ref "C24") (pin "2") (pinfunction "2_2") (pintype "passive"))
      (node (ref "U6") (pin "11") (pinfunction "VCP_11") (pintype "passive"))
    )
    (net (code "54") (name "Net-(U6-VINT)") (class "Default")
      (node (ref "C25") (pin "1") (pinfunction "1_1") (pintype "passive"))
      (node (ref "U6") (pin "14") (pinfunction "VINT_14") (pintype "passive"))
    )
    (net (code "55") (name "USB_DETECT") (class "Default")
      (node (ref "R7") (pin "1") (pinfunction "1_1") (pintype "passive"))
      (node (ref "R8") (pin "2") (pinfunction "2_2") (pintype "passive"))
      (node (ref "U1") (pin "35") (pinfunction "PA5/PGMRDY_35") (pintype "bidirectional"))
      (node (ref "USB_DETECT_TP") (pin "1") (pinfunction "1_1") (pintype "passive"))
    )
    (net (code "56") (name "VBUS") (class "Default")
      (node (ref "H3") (pin "1") (pinfunction "VBUS_1") (pintype "power_in"))
      (node (ref "R7") (pin "2") (pinfunction "2_2") (pintype "passive"))
      (node (ref "VBUS_TP") (pin "1") (pinfunction "1_1") (pintype "passive"))
    )
    (net (code "57") (name "V_BAT") (class "Default")
      (node (ref "C23") (pin "1") (pinfunction "1_1") (pintype "passive"))
      (node (ref "C24") (pin "1") (pinfunction "1_1") (pintype "passive"))
      (node (ref "C3") (pin "2") (pinfunction "2_2") (pintype "passive"))
      (node (ref "Q1") (pin "2") (pinfunction "2_2") (pintype "passive"))
      (node (ref "R14") (pin "2") (pinfunction "2_2") (pintype "passive"))
      (node (ref "R3") (pin "2") (pinfunction "2_2") (pintype "passive"))
      (node (ref "U2") (pin "2") (pinfunction "VIN_2") (pintype "input"))
      (node (ref "U2") (pin "3") (pinfunction "EN_3") (pintype "output"))
      (node (ref "U6") (pin "12") (pinfunction "VM_12") (pintype "passive"))
      (node (ref "V_BATT_TP") (pin "1") (pinfunction "1_1") (pintype "passive"))
    )
    (net (code "58") (name "unconnected-(H2-Pad3)") (class "Default")
      (node (ref "H2") (pin "3") (pinfunction "3_3") (pintype "passive+no_connect"))
    )
    (net (code "59") (name "unconnected-(H2-Pad9)") (class "Default")
      (node (ref "H2") (pin "9") (pinfunction "9_9") (pintype "passive+no_connect"))
    )
    (net (code "60") (name "unconnected-(H2-Pad10)") (class "Default")
      (node (ref "H2") (pin "10") (pinfunction "10_10") (pintype "passive+no_connect"))
    )
    (net (code "61") (name "unconnected-(H3-ID-Pad4)") (class "Default")
      (node (ref "H3") (pin "4") (pinfunction "ID_4") (pintype "power_in"))
    )
    (net (code "62") (name "unconnected-(H5-Pad2)") (class "Default")
      (node (ref "H5") (pin "2") (pinfunction "2_2") (pintype "passive"))
    )
    (net (code "63") (name "unconnected-(H10-Pad3)") (class "Default")
      (node (ref "H10") (pin "3") (pinfunction "3_3") (pintype "passive+no_connect"))
    )
    (net (code "64") (name "unconnected-(H10-Pad8)") (class "Default")
      (node (ref "H10") (pin "8") (pinfunction "8_8") (pintype "passive+no_connect"))
    )
    (net (code "65") (name "unconnected-(U1A-JTAGSEL-Pad50)") (class "Default")
      (node (ref "U1") (pin "50") (pinfunction "JTAGSEL_50") (pintype "input+no_connect"))
    )
    (net (code "66") (name "unconnected-(U1A-PA6{slash}PGMNOE-Pad34)") (class "Default")
      (node (ref "U1") (pin "34") (pinfunction "PA6/PGMNOE_34") (pintype "bidirectional"))
    )
    (net (code "67") (name "unconnected-(U1A-PA7{slash}XIN32{slash}PGMNVALID-Pad32)") (class "Default")
      (node (ref "U1") (pin "32") (pinfunction "PA7/XIN32/PGMNVALID_32") (pintype "bidirectional+no_connect"))
    )
    (net (code "68") (name "unconnected-(U1A-PA8{slash}XOUT32{slash}PGMM0-Pad31)") (class "Default")
      (node (ref "U1") (pin "31") (pinfunction "PA8/XOUT32/PGMM0_31") (pintype "bidirectional+no_connect"))
    )
    (net (code "69") (name "unconnected-(U1A-PA10{slash}PGMM2-Pad29)") (class "Default")
      (node (ref "U1") (pin "29") (pinfunction "PA10/PGMM2_29") (pintype "bidirectional+no_connect"))
    )
    (net (code "70") (name "unconnected-(U1A-PA16{slash}PGMD4-Pad19)") (class "Default")
      (node (ref "U1") (pin "19") (pinfunction "PA16/PGMD4_19") (pintype "bidirectional+no_connect"))
    )
    (net (code "71") (name "unconnected-(U1A-PA21{slash}PGMD9{slash}AD8-Pad11)") (class "Default")
      (node (ref "U1") (pin "11") (pinfunction "PA21/PGMD9/AD8_11") (pintype "bidirectional+no_connect"))
    )
    (net (code "72") (name "unconnected-(U1A-PA22{slash}PGMD10{slash}AD9-Pad14)") (class "Default")
      (node (ref "U1") (pin "14") (pinfunction "PA22/PGMD10/AD9_14") (pintype "bidirectional+no_connect"))
    )
    (net (code "73") (name "unconnected-(U1A-PA23{slash}PGMD11-Pad15)") (class "Default")
      (node (ref "U1") (pin "15") (pinfunction "PA23/PGMD11_15") (pintype "bidirectional+no_connect"))
    )
    (net (code "74") (name "unconnected-(U1A-PA24{slash}PGMD12-Pad23)") (class "Default")
      (node (ref "U1") (pin "23") (pinfunction "PA24/PGMD12_23") (pintype "bidirectional+no_connect"))
    )
    (net (code "75") (name "unconnected-(U1A-PB1{slash}AD5-Pad4)") (class "Default")
      (node (ref "U1") (pin "4") (pinfunction "PB1/AD5_4") (pintype "bidirectional+no_connect"))
    )
    (net (code "76") (name "unconnected-(U1A-PB2{slash}AD6-Pad5)") (class "Default")
      (node (ref "U1") (pin "5") (pinfunction "PB2/AD6_5") (pintype "bidirectional+no_connect"))
    )
    (net (code "77") (name "unconnected-(U1A-PB3{slash}AD7-Pad6)") (class "Default")
      (node (ref "U1") (pin "6") (pinfunction "PB3/AD7_6") (pintype "bidirectional+no_connect"))
    )
    (net (code "78") (name "unconnected-(U1A-PB13{slash}DAC0-Pad59)") (class "Default")
      (node (ref "U1") (pin "59") (pinfunction "PB13/DAC0_59") (pintype "bidirectional+no_connect"))
    )
    (net (code "79") (name "unconnected-(U1A-PB14{slash}DAC1-Pad63)") (class "Default")
      (node (ref "U1") (pin "63") (pinfunction "PB14/DAC1_63") (pintype "bidirectional+no_connect"))
    )
    (net (code "80") (name "unconnected-(U1A-TDI{slash}PB4-Pad33)") (class "Default")
      (node (ref "U1") (pin "33") (pinfunction "TDI/PB4_33") (pintype "bidirectional+no_connect"))
    )
    (net (code "81") (name "unconnected-(U1A-TDO{slash}TRACESWO{slash}PB5-Pad49)") (class "Default")
      (node (ref "U1") (pin "49") (pinfunction "TDO/TRACESWO/PB5_49") (pintype "bidirectional+no_connect"))
    )
    (net (code "82") (name "unconnected-(U1A-TST-Pad40)") (class "Default")
      (node (ref "U1") (pin "40") (pinfunction "TST_40") (pintype "input+no_connect"))
    )
    (net (code "83") (name "unconnected-(U2-NC-Pad6)") (class "Default")
      (node (ref "U2") (pin "6") (pinfunction "NC_6") (pintype "passive+no_connect"))
    )
    (net (code "84") (name "unconnected-(U4-BYP-Pad4)") (class "Default")
      (node (ref "U4") (pin "4") (pinfunction "BYP_4") (pintype "passive"))
    )
    (net (code "85") (name "unconnected-(U5-BYP-Pad4)") (class "Default")
      (node (ref "U5") (pin "4") (pinfunction "BYP_4") (pintype "passive"))
    )
  )
)
